# gps_blk.net
KiCad netlist of a schematic drawn in Altium Designer
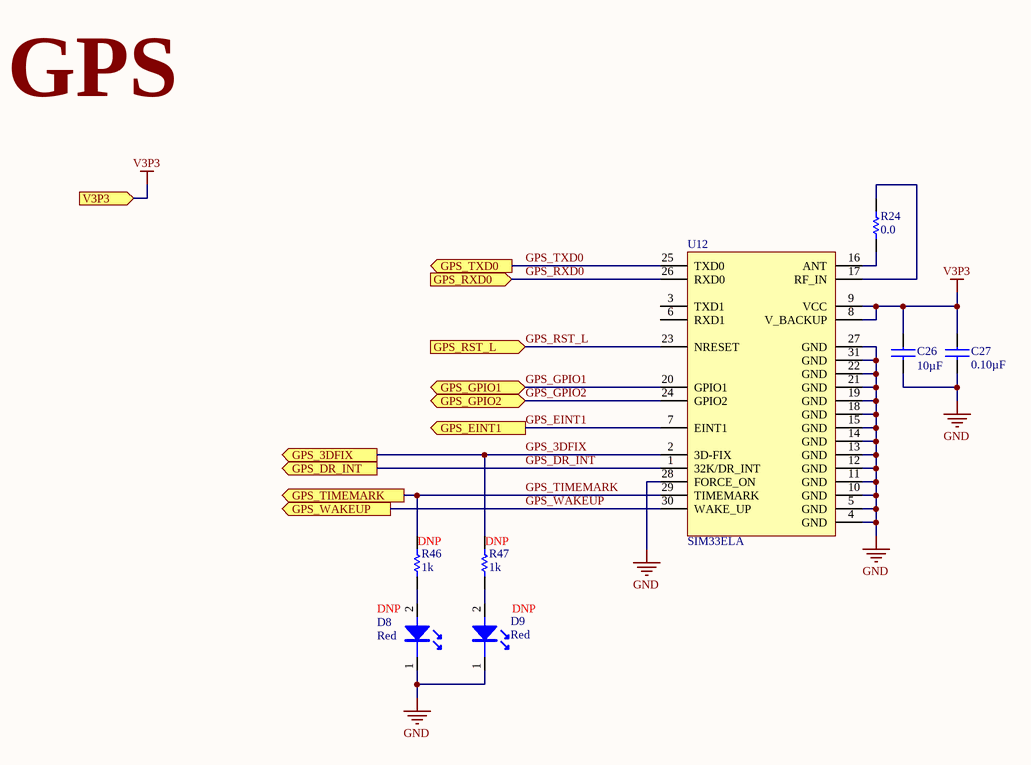
[diagram p0: gps_blk.SchDoc]

(export (version "E")
  (design (tool "Eeschema 10.0.6"))
  (components
    (comp (ref "C26")
      (value "10µF")
      (footprint "C1206")
      (description "CAP CER 10UF 16V X7R 1206")
      (fields (field (name "MPN") "GRM31CR71C106KAC7L"))
      (libsource (lib "Capacitor") (part "GRM31CR71C106KAC7L"))
    )
    (comp (ref "C27")
      (value "0.10µF")
      (footprint "C0402")
      (description "CAP CER 0.1UF 50V X7R 0402")
      (fields (field (name "MPN") "GRM155R71H104ME14D"))
      (libsource (lib "Capacitor") (part "GRM155R71H104ME14D"))
    )
    (comp (ref "D8")
      (value "Red")
      (footprint "LED0402(RED)")
      (description "LED RED 0402 SMD")
      (fields (field (name "MPN") "VLMS1500-GS08") (field (name "LOAD") "DNP"))
      (libsource (lib "Diode") (part "VLMS1500-GS08"))
    )
    (comp (ref "D9")
      (value "Red")
      (footprint "LED0402(RED)")
      (description "LED RED 0402 SMD")
      (fields (field (name "MPN") "VLMS1500-GS08") (field (name "LOAD") "DNP"))
      (libsource (lib "Diode") (part "VLMS1500-GS08"))
    )
    (comp (ref "R24")
      (value "0.0")
      (footprint "R0603")
      (description "RES SMD 0.0OHM JUMPER 1/10W 0603")
      (fields (field (name "MPN") "CRCW06030000Z0EA"))
      (libsource (lib "Res") (part "CRCW06030000Z0EA"))
    )
    (comp (ref "R46")
      (value "1k")
      (footprint "R0402")
      (description "RES SMD 1K OHM 1% 1/10W 0402")
      (fields (field (name "MPN") "ERJ-2RKF1001X") (field (name "LOAD") "DNP"))
      (libsource (lib "Res") (part "ERJ-2RKF1001X"))
    )
    (comp (ref "R47")
      (value "1k")
      (footprint "R0402")
      (description "RES SMD 1K OHM 1% 1/10W 0402")
      (fields (field (name "MPN") "ERJ-2RKF1001X") (field (name "LOAD") "DNP"))
      (libsource (lib "Res") (part "ERJ-2RKF1001X"))
    )
    (comp (ref "U12")
      (value "SIM33ELA")
      (footprint "SIM33ELA")
      (description "A-GPS receiver, with built-in Antenna")
      (fields (field (name "MPN") "SIM33ELA"))
      (libsource (lib "IC") (part "SIM33ELA"))
    )
  )
  (nets
    (net (code "1") (name "/GPS_3DFIX") (class "Default")
      (node (ref "R47") (pin "2") (pinfunction "2_2") (pintype "passive"))
      (node (ref "U12") (pin "2") (pinfunction "3D-FIX_2") (pintype "passive"))
    )
    (net (code "2") (name "/GPS_DR_INT") (class "Default")
      (node (ref "U12") (pin "1") (pinfunction "32K/DR_INT_1") (pintype "passive"))
    )
    (net (code "3") (name "/GPS_EINT1") (class "Default")
      (node (ref "U12") (pin "7") (pinfunction "EINT1_7") (pintype "passive"))
    )
    (net (code "4") (name "/GPS_GPIO1") (class "Default")
      (node (ref "U12") (pin "20") (pinfunction "GPIO1_20") (pintype "passive"))
    )
    (net (code "5") (name "/GPS_GPIO2") (class "Default")
      (node (ref "U12") (pin "24") (pinfunction "GPIO2_24") (pintype "passive"))
    )
    (net (code "6") (name "/GPS_RST_L") (class "Default")
      (node (ref "U12") (pin "23") (pinfunction "NRESET_23") (pintype "passive"))
    )
    (net (code "7") (name "/GPS_RXD0") (class "Default")
      (node (ref "U12") (pin "26") (pinfunction "RXD0_26") (pintype "passive"))
    )
    (net (code "8") (name "/GPS_TIMEMARK") (class "Default")
      (node (ref "R46") (pin "2") (pinfunction "2_2") (pintype "passive"))
      (node (ref "U12") (pin "29") (pinfunction "TIMEMARK_29") (pintype "passive"))
    )
    (net (code "9") (name "/GPS_TXD0") (class "Default")
      (node (ref "U12") (pin "25") (pinfunction "TXD0_25") (pintype "passive"))
    )
    (net (code "10") (name "/GPS_WAKEUP") (class "Default")
      (node (ref "U12") (pin "30") (pinfunction "WAKE_UP_30") (pintype "passive"))
    )
    (net (code "11") (name "GND") (class "Default")
      (node (ref "C26") (pin "2") (pinfunction "2_2") (pintype "passive"))
      (node (ref "C27") (pin "2") (pinfunction "2_2") (pintype "passive"))
      (node (ref "D8") (pin "1") (pinfunction "1_1") (pintype "passive"))
      (node (ref "D9") (pin "1") (pinfunction "1_1") (pintype "passive"))
      (node (ref "U12") (pin "10") (pinfunction "GND_10") (pintype "passive"))
      (node (ref "U12") (pin "11") (pinfunction "GND_11") (pintype "passive"))
      (node (ref "U12") (pin "12") (pinfunction "GND_12") (pintype "passive"))
      (node (ref "U12") (pin "13") (pinfunction "GND_13") (pintype "passive"))
      (node (ref "U12") (pin "14") (pinfunction "GND_14") (pintype "passive"))
      (node (ref "U12") (pin "15") (pinfunction "GND_15") (pintype "passive"))
      (node (ref "U12") (pin "18") (pinfunction "GND_18") (pintype "passive"))
      (node (ref "U12") (pin "19") (pinfunction "GND_19") (pintype "passive"))
      (node (ref "U12") (pin "21") (pinfunction "GND_21") (pintype "passive"))
      (node (ref "U12") (pin "22") (pinfunction "GND_22") (pintype "passive"))
      (node (ref "U12") (pin "27") (pinfunction "GND_27") (pintype "passive"))
      (node (ref "U12") (pin "28") (pinfunction "FORCE_ON_28") (pintype "passive"))
      (node (ref "U12") (pin "31") (pinfunction "GND_31") (pintype "passive"))
      (node (ref "U12") (pin "4") (pinfunction "GND_4") (pintype "passive"))
      (node (ref "U12") (pin "5") (pinfunction "GND_5") (pintype "passive"))
    )
    (net (code "12") (name "Net-(D8-Pad2)") (class "Default")
      (node (ref "D8") (pin "2") (pinfunction "2_2") (pintype "passive"))
      (node (ref "R46") (pin "1") (pinfunction "1_1") (pintype "passive"))
    )
    (net (code "13") (name "Net-(D9-Pad2)") (class "Default")
      (node (ref "D9") (pin "2") (pinfunction "2_2") (pintype "passive"))
      (node (ref "R47") (pin "1") (pinfunction "1_1") (pintype "passive"))
    )
    (net (code "14") (name "Net-(U12-ANT)") (class "Default")
      (node (ref "R24") (pin "1") (pinfunction "1_1") (pintype "passive"))
      (node (ref "U12") (pin "16") (pinfunction "ANT_16") (pintype "passive"))
    )
    (net (code "15") (name "Net-(U12-RF_IN)") (class "Default")
      (node (ref "R24") (pin "2") (pinfunction "2_2") (pintype "passive"))
      (node (ref "U12") (pin "17") (pinfunction "RF_IN_17") (pintype "passive"))
    )
    (net (code "16") (name "V3P3") (class "Default")
      (node (ref "C26") (pin "1") (pinfunction "1_1") (pintype "passive"))
      (node (ref "C27") (pin "1") (pinfunction "1_1") (pintype "passive"))
      (node (ref "U12") (pin "8") (pinfunction "V_BACKUP_8") (pintype "passive"))
      (node (ref "U12") (pin "9") (pinfunction "VCC_9") (pintype "passive"))
    )
    (net (code "17") (name "unconnected-(U12-RXD1-Pad6)") (class "Default")
      (node (ref "U12") (pin "6") (pinfunction "RXD1_6") (pintype "passive"))
    )
    (net (code "18") (name "unconnected-(U12-TXD1-Pad3)") (class "Default")
      (node (ref "U12") (pin "3") (pinfunction "TXD1_3") (pintype "passive"))
    )
  )
)
